# question_1.net
KiCad netlist of a schematic drawn in EAGLE
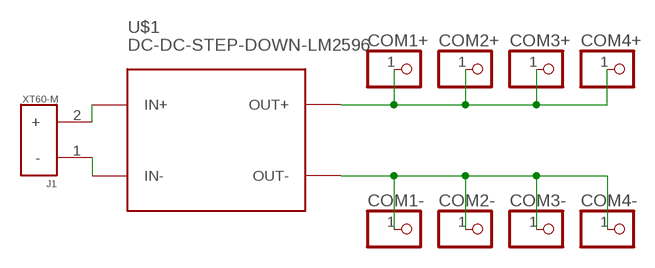
[diagram p0: schematic, sheet 1]

(export (version "E")
  (design (tool "Eeschema 10.0.6"))
  (components
    (comp (ref "COM1+")
      (value "PINHD-1X1")
      (footprint "eagle-import:1X01")
      (libsource (lib "eagle-import") (part "PINHD-1X1"))
    )
    (comp (ref "COM1-")
      (value "PINHD-1X1")
      (footprint "eagle-import:1X01")
      (libsource (lib "eagle-import") (part "PINHD-1X1"))
    )
    (comp (ref "COM2+")
      (value "PINHD-1X1")
      (footprint "eagle-import:1X01")
      (libsource (lib "eagle-import") (part "PINHD-1X1"))
    )
    (comp (ref "COM2-")
      (value "PINHD-1X1")
      (footprint "eagle-import:1X01")
      (libsource (lib "eagle-import") (part "PINHD-1X1"))
    )
    (comp (ref "COM3+")
      (value "PINHD-1X1")
      (footprint "eagle-import:1X01")
      (libsource (lib "eagle-import") (part "PINHD-1X1"))
    )
    (comp (ref "COM3-")
      (value "PINHD-1X1")
      (footprint "eagle-import:1X01")
      (libsource (lib "eagle-import") (part "PINHD-1X1"))
    )
    (comp (ref "COM4+")
      (value "PINHD-1X1")
      (footprint "eagle-import:1X01")
      (libsource (lib "eagle-import") (part "PINHD-1X1"))
    )
    (comp (ref "COM4-")
      (value "PINHD-1X1")
      (footprint "eagle-import:1X01")
      (libsource (lib "eagle-import") (part "PINHD-1X1"))
    )
    (comp (ref "J1")
      (value "XT60-M")
      (footprint "eagle-import:AMASS_XT60-M")
      (fields (field (name "MF") "AMASS"))
      (libsource (lib "eagle-import") (part "XT60-M"))
    )
    (comp (ref "U$1")
      (value "DC-DC-STEP-DOWN-LM2596")
      (footprint "eagle-import:DC-DC-STEP-DOWN-LM2596")
      (libsource (lib "eagle-import") (part "DC-DC-STEP-DOWN-LM2596"))
    )
  )
  (nets
    (net (code "1") (name "Net-(COM1+-Pad1)") (class "Default")
      (node (ref "COM1+") (pin "1") (pinfunction "1_1") (pintype "passive"))
      (node (ref "COM2+") (pin "1") (pinfunction "1_1") (pintype "passive"))
      (node (ref "COM3+") (pin "1") (pinfunction "1_1") (pintype "passive"))
      (node (ref "COM4+") (pin "1") (pinfunction "1_1") (pintype "passive"))
      (node (ref "U$1") (pin "OUT+") (pinfunction "OUT+_OUT+") (pintype "bidirectional"))
    )
    (net (code "2") (name "Net-(COM1--Pad1)") (class "Default")
      (node (ref "COM1-") (pin "1") (pinfunction "1_1") (pintype "passive"))
      (node (ref "COM2-") (pin "1") (pinfunction "1_1") (pintype "passive"))
      (node (ref "COM3-") (pin "1") (pinfunction "1_1") (pintype "passive"))
      (node (ref "COM4-") (pin "1") (pinfunction "1_1") (pintype "passive"))
      (node (ref "U$1") (pin "OUT-") (pinfunction "OUT-_OUT-") (pintype "bidirectional"))
    )
    (net (code "3") (name "Net-(J1-+)") (class "Default")
      (node (ref "J1") (pin "2") (pinfunction "+_2") (pintype "passive"))
      (node (ref "U$1") (pin "IN+") (pinfunction "IN+_IN+") (pintype "bidirectional"))
    )
    (net (code "4") (name "Net-(J1--)") (class "Default")
      (node (ref "J1") (pin "1") (pinfunction "-_1") (pintype "passive"))
      (node (ref "U$1") (pin "IN-") (pinfunction "IN-_IN-") (pintype "bidirectional"))
    )
  )
)
